# super_como_r1.net
KiCad netlist of a schematic drawn in EAGLE
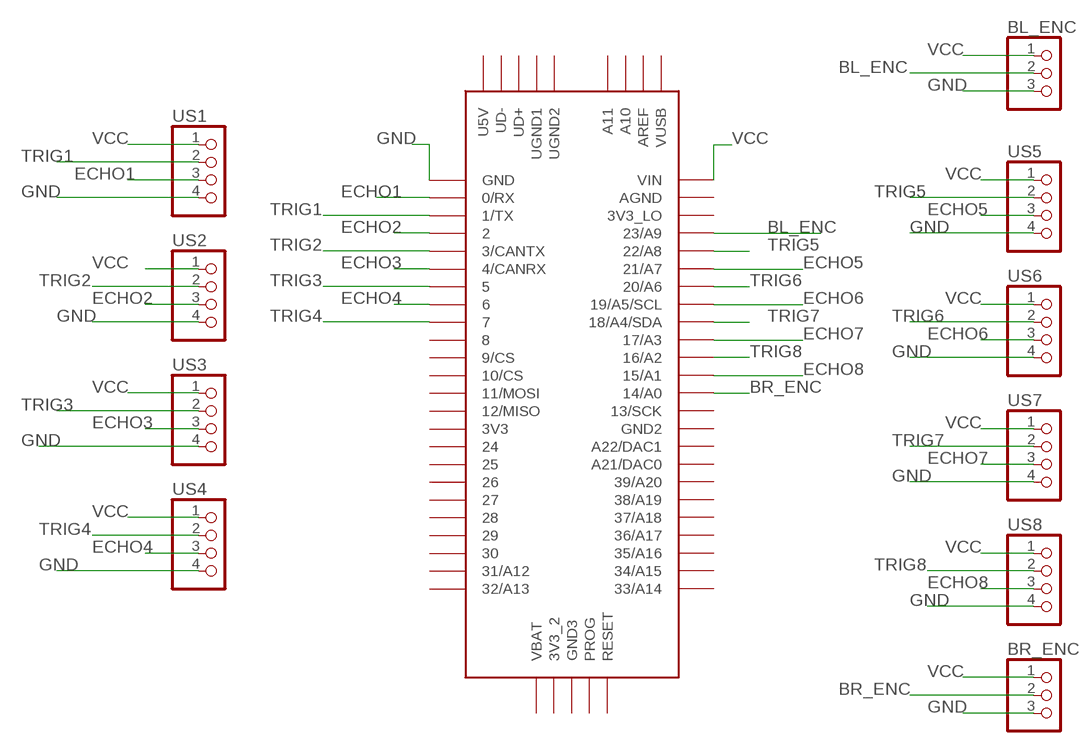
[diagram p0: schematic, sheet 1]

(export (version "E")
  (design (tool "Eeschema 10.0.6"))
  (components
    (comp (ref "BL_ENC")
      (value "PINHD-1X3/90")
      (footprint "eagle-import:1X03_90")
      (libsource (lib "eagle-import") (part "PINHD-1X3/90"))
    )
    (comp (ref "BR_ENC")
      (value "PINHD-1X3/90")
      (footprint "eagle-import:1X03_90")
      (libsource (lib "eagle-import") (part "PINHD-1X3/90"))
    )
    (comp (ref "U$1")
      (value "TEENSY_3.5/3.6")
      (footprint "eagle-import:TEENSY_3.5_3.6")
      (libsource (lib "eagle-import") (part "TEENSY_3.5/3.6"))
    )
    (comp (ref "US1")
      (value "PINHD-1X4/90")
      (footprint "eagle-import:1X04_90")
      (libsource (lib "eagle-import") (part "PINHD-1X4/90"))
    )
    (comp (ref "US2")
      (value "PINHD-1X4/90")
      (footprint "eagle-import:1X04_90")
      (libsource (lib "eagle-import") (part "PINHD-1X4/90"))
    )
    (comp (ref "US3")
      (value "PINHD-1X4/90")
      (footprint "eagle-import:1X04_90")
      (libsource (lib "eagle-import") (part "PINHD-1X4/90"))
    )
    (comp (ref "US4")
      (value "PINHD-1X4/90")
      (footprint "eagle-import:1X04_90")
      (libsource (lib "eagle-import") (part "PINHD-1X4/90"))
    )
    (comp (ref "US5")
      (value "PINHD-1X4/90")
      (footprint "eagle-import:1X04_90")
      (libsource (lib "eagle-import") (part "PINHD-1X4/90"))
    )
    (comp (ref "US6")
      (value "PINHD-1X4/90")
      (footprint "eagle-import:1X04_90")
      (libsource (lib "eagle-import") (part "PINHD-1X4/90"))
    )
    (comp (ref "US7")
      (value "PINHD-1X4/90")
      (footprint "eagle-import:1X04_90")
      (libsource (lib "eagle-import") (part "PINHD-1X4/90"))
    )
    (comp (ref "US8")
      (value "PINHD-1X4/90")
      (footprint "eagle-import:1X04_90")
      (libsource (lib "eagle-import") (part "PINHD-1X4/90"))
    )
  )
  (nets
    (net (code "1") (name "/BL_ENC") (class "Default")
      (node (ref "BL_ENC") (pin "2") (pinfunction "2_2") (pintype "passive"))
      (node (ref "U$1") (pin "23/A9") (pinfunction "23/A9_23/A9") (pintype "bidirectional"))
    )
    (net (code "2") (name "/BR_ENC") (class "Default")
      (node (ref "BR_ENC") (pin "2") (pinfunction "2_2") (pintype "passive"))
      (node (ref "U$1") (pin "14/A0") (pinfunction "14/A0_14/A0") (pintype "bidirectional"))
    )
    (net (code "3") (name "/ECHO1") (class "Default")
      (node (ref "U$1") (pin "0/RX") (pinfunction "0/RX_0/RX") (pintype "bidirectional"))
      (node (ref "US1") (pin "3") (pinfunction "3_3") (pintype "passive"))
    )
    (net (code "4") (name "/ECHO2") (class "Default")
      (node (ref "U$1") (pin "2") (pinfunction "2_2") (pintype "bidirectional"))
      (node (ref "US2") (pin "3") (pinfunction "3_3") (pintype "passive"))
    )
    (net (code "5") (name "/ECHO3") (class "Default")
      (node (ref "U$1") (pin "4/CANRX") (pinfunction "4/CANRX_4/CANRX") (pintype "bidirectional"))
      (node (ref "US3") (pin "3") (pinfunction "3_3") (pintype "passive"))
    )
    (net (code "6") (name "/ECHO4") (class "Default")
      (node (ref "U$1") (pin "6") (pinfunction "6_6") (pintype "bidirectional"))
      (node (ref "US4") (pin "3") (pinfunction "3_3") (pintype "passive"))
    )
    (net (code "7") (name "/ECHO5") (class "Default")
      (node (ref "U$1") (pin "21/A7") (pinfunction "21/A7_21/A7") (pintype "bidirectional"))
      (node (ref "US5") (pin "3") (pinfunction "3_3") (pintype "passive"))
    )
    (net (code "8") (name "/ECHO6") (class "Default")
      (node (ref "U$1") (pin "19/A5/SCL") (pinfunction "19/A5/SCL_19/A5/SCL") (pintype "bidirectional"))
      (node (ref "US6") (pin "3") (pinfunction "3_3") (pintype "passive"))
    )
    (net (code "9") (name "/ECHO7") (class "Default")
      (node (ref "U$1") (pin "17/A3") (pinfunction "17/A3_17/A3") (pintype "bidirectional"))
      (node (ref "US7") (pin "3") (pinfunction "3_3") (pintype "passive"))
    )
    (net (code "10") (name "/ECHO8") (class "Default")
      (node (ref "U$1") (pin "15/A1") (pinfunction "15/A1_15/A1") (pintype "bidirectional"))
      (node (ref "US8") (pin "3") (pinfunction "3_3") (pintype "passive"))
    )
    (net (code "11") (name "/GND") (class "Default")
      (node (ref "BL_ENC") (pin "3") (pinfunction "3_3") (pintype "passive"))
      (node (ref "BR_ENC") (pin "3") (pinfunction "3_3") (pintype "passive"))
      (node (ref "U$1") (pin "GND") (pinfunction "GND_GND") (pintype "bidirectional"))
      (node (ref "US1") (pin "4") (pinfunction "4_4") (pintype "passive"))
      (node (ref "US2") (pin "4") (pinfunction "4_4") (pintype "passive"))
      (node (ref "US3") (pin "4") (pinfunction "4_4") (pintype "passive"))
      (node (ref "US4") (pin "4") (pinfunction "4_4") (pintype "passive"))
      (node (ref "US5") (pin "4") (pinfunction "4_4") (pintype "passive"))
      (node (ref "US6") (pin "4") (pinfunction "4_4") (pintype "passive"))
      (node (ref "US7") (pin "4") (pinfunction "4_4") (pintype "passive"))
      (node (ref "US8") (pin "4") (pinfunction "4_4") (pintype "passive"))
    )
    (net (code "12") (name "/TRIG1") (class "Default")
      (node (ref "U$1") (pin "1/TX") (pinfunction "1/TX_1/TX") (pintype "bidirectional"))
      (node (ref "US1") (pin "2") (pinfunction "2_2") (pintype "passive"))
    )
    (net (code "13") (name "/TRIG2") (class "Default")
      (node (ref "U$1") (pin "3/CANTX") (pinfunction "3/CANTX_3/CANTX") (pintype "bidirectional"))
      (node (ref "US2") (pin "2") (pinfunction "2_2") (pintype "passive"))
    )
    (net (code "14") (name "/TRIG3") (class "Default")
      (node (ref "U$1") (pin "5") (pinfunction "5_5") (pintype "bidirectional"))
      (node (ref "US3") (pin "2") (pinfunction "2_2") (pintype "passive"))
    )
    (net (code "15") (name "/TRIG4") (class "Default")
      (node (ref "U$1") (pin "7") (pinfunction "7_7") (pintype "bidirectional"))
      (node (ref "US4") (pin "2") (pinfunction "2_2") (pintype "passive"))
    )
    (net (code "16") (name "/TRIG5") (class "Default")
      (node (ref "U$1") (pin "22/A8") (pinfunction "22/A8_22/A8") (pintype "bidirectional"))
      (node (ref "US5") (pin "2") (pinfunction "2_2") (pintype "passive"))
    )
    (net (code "17") (name "/TRIG6") (class "Default")
      (node (ref "U$1") (pin "20/A6") (pinfunction "20/A6_20/A6") (pintype "bidirectional"))
      (node (ref "US6") (pin "2") (pinfunction "2_2") (pintype "passive"))
    )
    (net (code "18") (name "/TRIG7") (class "Default")
      (node (ref "U$1") (pin "18/A4/SDA") (pinfunction "18/A4/SDA_18/A4/SDA") (pintype "bidirectional"))
      (node (ref "US7") (pin "2") (pinfunction "2_2") (pintype "passive"))
    )
    (net (code "19") (name "/TRIG8") (class "Default")
      (node (ref "U$1") (pin "16/A2") (pinfunction "16/A2_16/A2") (pintype "bidirectional"))
      (node (ref "US8") (pin "2") (pinfunction "2_2") (pintype "passive"))
    )
    (net (code "20") (name "/VCC") (class "Default")
      (node (ref "BL_ENC") (pin "1") (pinfunction "1_1") (pintype "passive"))
      (node (ref "BR_ENC") (pin "1") (pinfunction "1_1") (pintype "passive"))
      (node (ref "U$1") (pin "VIN") (pinfunction "VIN_VIN") (pintype "bidirectional"))
      (node (ref "US1") (pin "1") (pinfunction "1_1") (pintype "passive"))
      (node (ref "US2") (pin "1") (pinfunction "1_1") (pintype "passive"))
      (node (ref "US3") (pin "1") (pinfunction "1_1") (pintype "passive"))
      (node (ref "US4") (pin "1") (pinfunction "1_1") (pintype "passive"))
      (node (ref "US5") (pin "1") (pinfunction "1_1") (pintype "passive"))
      (node (ref "US6") (pin "1") (pinfunction "1_1") (pintype "passive"))
      (node (ref "US7") (pin "1") (pinfunction "1_1") (pintype "passive"))
      (node (ref "US8") (pin "1") (pinfunction "1_1") (pintype "passive"))
    )
    (net (code "21") (name "unconnected-(U$1-A21{slash}DAC0-Pad21{slash}DAC0)") (class "Default")
      (node (ref "U$1") (pin "21/DAC0") (pinfunction "A21/DAC0_21/DAC0") (pintype "bidirectional"))
    )
    (net (code "22") (name "unconnected-(U$1-Pad3V3)") (class "Default")
      (node (ref "U$1") (pin "3V3") (pinfunction "3V3_3V3") (pintype "bidirectional"))
    )
    (net (code "23") (name "unconnected-(U$1-Pad3V3_2)") (class "Default")
      (node (ref "U$1") (pin "3V3_2") (pinfunction "3V3_2_3V3_2") (pintype "bidirectional"))
    )
    (net (code "24") (name "unconnected-(U$1-Pad3V3_LO)") (class "Default")
      (node (ref "U$1") (pin "3V3_LO") (pinfunction "3V3_LO_3V3_LO") (pintype "bidirectional"))
    )
    (net (code "25") (name "unconnected-(U$1-Pad8)") (class "Default")
      (node (ref "U$1") (pin "8") (pinfunction "8_8") (pintype "bidirectional"))
    )
    (net (code "26") (name "unconnected-(U$1-Pad9{slash}CS)") (class "Default")
      (node (ref "U$1") (pin "9/CS") (pinfunction "9/CS_9/CS") (pintype "bidirectional"))
    )
    (net (code "27") (name "unconnected-(U$1-Pad10{slash}CS)") (class "Default")
      (node (ref "U$1") (pin "10/CS") (pinfunction "10/CS_10/CS") (pintype "bidirectional"))
    )
    (net (code "28") (name "unconnected-(U$1-Pad11{slash}MOSI)") (class "Default")
      (node (ref "U$1") (pin "11/MOSI") (pinfunction "11/MOSI_11/MOSI") (pintype "bidirectional"))
    )
    (net (code "29") (name "unconnected-(U$1-Pad12{slash}MISO)") (class "Default")
      (node (ref "U$1") (pin "12/MISO") (pinfunction "12/MISO_12/MISO") (pintype "bidirectional"))
    )
    (net (code "30") (name "unconnected-(U$1-Pad13{slash}SCK)") (class "Default")
      (node (ref "U$1") (pin "13/SCK") (pinfunction "13/SCK_13/SCK") (pintype "bidirectional"))
    )
    (net (code "31") (name "unconnected-(U$1-Pad24)") (class "Default")
      (node (ref "U$1") (pin "24") (pinfunction "24_24") (pintype "bidirectional"))
    )
    (net (code "32") (name "unconnected-(U$1-Pad25)") (class "Default")
      (node (ref "U$1") (pin "25") (pinfunction "25_25") (pintype "bidirectional"))
    )
    (net (code "33") (name "unconnected-(U$1-Pad26)") (class "Default")
      (node (ref "U$1") (pin "26") (pinfunction "26_26") (pintype "bidirectional"))
    )
    (net (code "34") (name "unconnected-(U$1-Pad27)") (class "Default")
      (node (ref "U$1") (pin "27") (pinfunction "27_27") (pintype "bidirectional"))
    )
    (net (code "35") (name "unconnected-(U$1-Pad28)") (class "Default")
      (node (ref "U$1") (pin "28") (pinfunction "28_28") (pintype "bidirectional"))
    )
    (net (code "36") (name "unconnected-(U$1-Pad29)") (class "Default")
      (node (ref "U$1") (pin "29") (pinfunction "29_29") (pintype "bidirectional"))
    )
    (net (code "37") (name "unconnected-(U$1-Pad30)") (class "Default")
      (node (ref "U$1") (pin "30") (pinfunction "30_30") (pintype "bidirectional"))
    )
    (net (code "38") (name "unconnected-(U$1-Pad31{slash}A12)") (class "Default")
      (node (ref "U$1") (pin "31/A12") (pinfunction "31/A12_31/A12") (pintype "bidirectional"))
    )
    (net (code "39") (name "unconnected-(U$1-Pad32{slash}A13)") (class "Default")
      (node (ref "U$1") (pin "32/A13") (pinfunction "32/A13_32/A13") (pintype "bidirectional"))
    )
    (net (code "40") (name "unconnected-(U$1-Pad33{slash}A14)") (class "Default")
      (node (ref "U$1") (pin "33/A14") (pinfunction "33/A14_33/A14") (pintype "bidirectional"))
    )
    (net (code "41") (name "unconnected-(U$1-Pad34{slash}A15)") (class "Default")
      (node (ref "U$1") (pin "34/A15") (pinfunction "34/A15_34/A15") (pintype "bidirectional"))
    )
    (net (code "42") (name "unconnected-(U$1-Pad35{slash}A16)") (class "Default")
      (node (ref "U$1") (pin "35/A16") (pinfunction "35/A16_35/A16") (pintype "bidirectional"))
    )
    (net (code "43") (name "unconnected-(U$1-Pad36{slash}A17)") (class "Default")
      (node (ref "U$1") (pin "36/A17") (pinfunction "36/A17_36/A17") (pintype "bidirectional"))
    )
    (net (code "44") (name "unconnected-(U$1-Pad37{slash}A18)") (class "Default")
      (node (ref "U$1") (pin "37/A18") (pinfunction "37/A18_37/A18") (pintype "bidirectional"))
    )
    (net (code "45") (name "unconnected-(U$1-Pad38{slash}A19)") (class "Default")
      (node (ref "U$1") (pin "38/A19") (pinfunction "38/A19_38/A19") (pintype "bidirectional"))
    )
    (net (code "46") (name "unconnected-(U$1-Pad39{slash}A20)") (class "Default")
      (node (ref "U$1") (pin "39/A20") (pinfunction "39/A20_39/A20") (pintype "bidirectional"))
    )
    (net (code "47") (name "unconnected-(U$1-PadA10)") (class "Default")
      (node (ref "U$1") (pin "A10") (pinfunction "A10_A10") (pintype "bidirectional"))
    )
    (net (code "48") (name "unconnected-(U$1-PadA11)") (class "Default")
      (node (ref "U$1") (pin "A11") (pinfunction "A11_A11") (pintype "bidirectional"))
    )
    (net (code "49") (name "unconnected-(U$1-PadA22{slash}DAC1)") (class "Default")
      (node (ref "U$1") (pin "A22/DAC1") (pinfunction "A22/DAC1_A22/DAC1") (pintype "bidirectional"))
    )
    (net (code "50") (name "unconnected-(U$1-PadAGND)") (class "Default")
      (node (ref "U$1") (pin "AGND") (pinfunction "AGND_AGND") (pintype "bidirectional"))
    )
    (net (code "51") (name "unconnected-(U$1-PadAREF)") (class "Default")
      (node (ref "U$1") (pin "AREF") (pinfunction "AREF_AREF") (pintype "bidirectional"))
    )
    (net (code "52") (name "unconnected-(U$1-PadGND2)") (class "Default")
      (node (ref "U$1") (pin "GND2") (pinfunction "GND2_GND2") (pintype "bidirectional"))
    )
    (net (code "53") (name "unconnected-(U$1-PadGND3)") (class "Default")
      (node (ref "U$1") (pin "GND3") (pinfunction "GND3_GND3") (pintype "bidirectional"))
    )
    (net (code "54") (name "unconnected-(U$1-PadPROG)") (class "Default")
      (node (ref "U$1") (pin "PROG") (pinfunction "PROG_PROG") (pintype "bidirectional"))
    )
    (net (code "55") (name "unconnected-(U$1-PadRESET)") (class "Default")
      (node (ref "U$1") (pin "RESET") (pinfunction "RESET_RESET") (pintype "bidirectional"))
    )
    (net (code "56") (name "unconnected-(U$1-PadU5V)") (class "Default")
      (node (ref "U$1") (pin "U5V") (pinfunction "U5V_U5V") (pintype "bidirectional"))
    )
    (net (code "57") (name "unconnected-(U$1-PadUD+)") (class "Default")
      (node (ref "U$1") (pin "UD+") (pinfunction "UD+_UD+") (pintype "bidirectional"))
    )
    (net (code "58") (name "unconnected-(U$1-PadUD-)") (class "Default")
      (node (ref "U$1") (pin "UD-") (pinfunction "UD-_UD-") (pintype "bidirectional"))
    )
    (net (code "59") (name "unconnected-(U$1-PadUGND1)") (class "Default")
      (node (ref "U$1") (pin "UGND1") (pinfunction "UGND1_UGND1") (pintype "bidirectional"))
    )
    (net (code "60") (name "unconnected-(U$1-PadUGND2)") (class "Default")
      (node (ref "U$1") (pin "UGND2") (pinfunction "UGND2_UGND2") (pintype "bidirectional"))
    )
    (net (code "61") (name "unconnected-(U$1-PadVBAT)") (class "Default")
      (node (ref "U$1") (pin "VBAT") (pinfunction "VBAT_VBAT") (pintype "bidirectional"))
    )
    (net (code "62") (name "unconnected-(U$1-PadVUSB)") (class "Default")
      (node (ref "U$1") (pin "VUSB") (pinfunction "VUSB_VUSB") (pintype "bidirectional"))
    )
  )
)
